# COMMUNICATION.net
KiCad netlist of a schematic drawn in Altium Designer
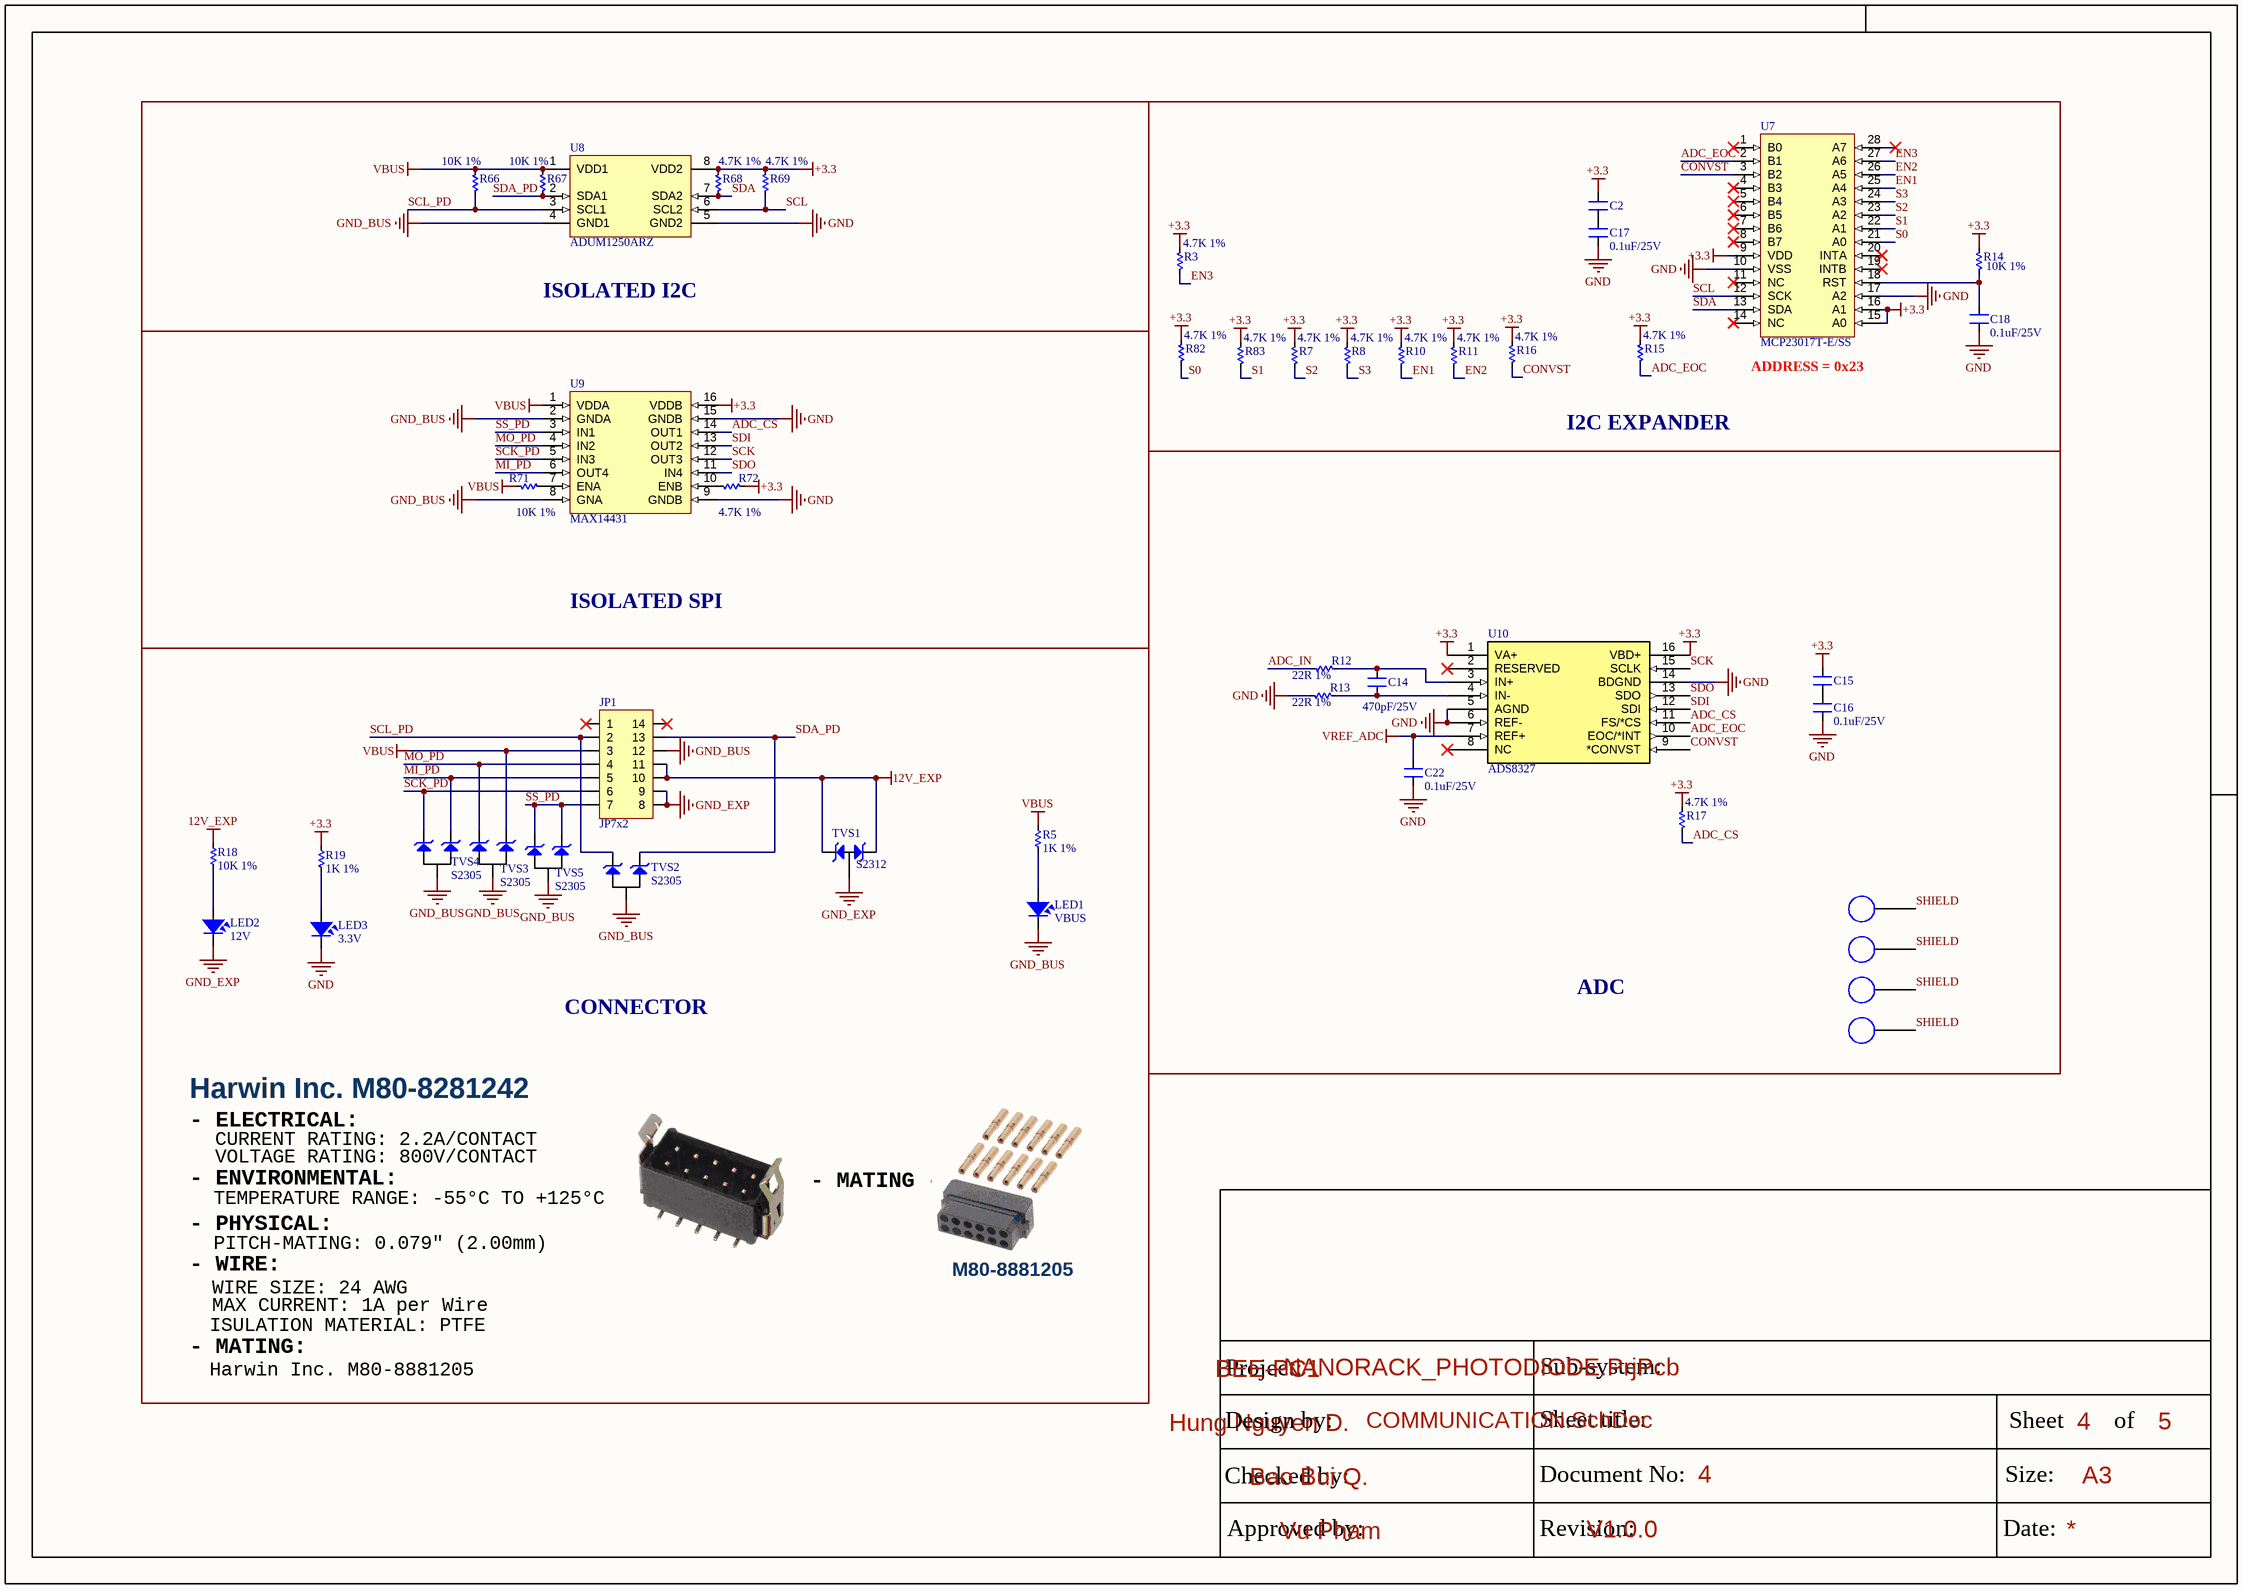
[diagram p0: COMMUNICATION.SchDoc]

(export (version "E")
  (design (tool "Eeschema 10.0.6"))
  (components
    (comp (ref "C2")
      (value "0.1uF/25V")
      (footprint "SM-0603")
      (description "0603")
      (libsource (lib "Capacitors") (part "CM"))
    )
    (comp (ref "C14")
      (value "470pF/25V")
      (footprint "SM-0603")
      (description "0603")
      (libsource (lib "Capacitors") (part "CM"))
    )
    (comp (ref "C15")
      (value "0.1uF/25V")
      (footprint "SM-0603")
      (description "0603")
      (libsource (lib "Capacitors") (part "CM"))
    )
    (comp (ref "C16")
      (value "0.1uF/25V")
      (footprint "SM-0603")
      (description "0603")
      (libsource (lib "Capacitors") (part "CM"))
    )
    (comp (ref "C17")
      (value "0.1uF/25V")
      (footprint "SM-0603")
      (description "0603")
      (libsource (lib "Capacitors") (part "CM"))
    )
    (comp (ref "C18")
      (value "0.1uF/25V")
      (footprint "SM-0603")
      (description "0603")
      (libsource (lib "Capacitors") (part "CM"))
    )
    (comp (ref "C22")
      (value "0.1uF/25V")
      (footprint "SM-0603")
      (description "0603")
      (libsource (lib "Capacitors") (part "CM"))
    )
    (comp (ref "H1") (value "M3") (footprint "M3") (libsource (lib "Library") (part "M3")))
    (comp (ref "H2") (value "M3") (footprint "M3") (libsource (lib "Library") (part "M3")))
    (comp (ref "H3") (value "M3") (footprint "M3") (libsource (lib "Library") (part "M3")))
    (comp (ref "H4") (value "M3") (footprint "M3") (libsource (lib "Library") (part "M3")))
    (comp (ref "JP1")
      (value "JP7x2")
      (footprint "M80-8281442")
      (description "WR-PHD 2.54 mm Dual Socket Header")
      (fields
        (field (name "MANUFACTURER") "Würth Elektronik eiSos GmbH")
        (field (name "PARTNO") "61301421821")
        (field (name "CREATED BY") "Karrer Zheng")
      )
      (libsource (lib "Library") (part "JP7x2"))
    )
    (comp (ref "LED1")
      (value "VBUS")
      (footprint "GREENLED_0603")
      (libsource (lib "Library") (part "LED SMD"))
    )
    (comp (ref "LED2") (value "12V") (footprint "GREENLED_0603") (libsource (lib "Library") (part "LED SMD")))
    (comp (ref "LED3")
      (value "3.3V")
      (footprint "GREENLED_0603")
      (libsource (lib "Library") (part "LED SMD"))
    )
    (comp (ref "R3")
      (value "4.7K 1%")
      (footprint "RES-SMD-0603")
      (description "0603")
      (fields
        (field (name "MANUFACTURER") "Generic Components")
        (field (name "PUBLISHER") "Altium Hobart Technology Centre")
      )
      (libsource (lib "Library") (part "Res-SMD"))
    )
    (comp (ref "R5")
      (value "1K 1%")
      (footprint "RES-SMD-0603")
      (description "0603")
      (fields
        (field (name "MANUFACTURER") "Generic Components")
        (field (name "PUBLISHER") "Altium Hobart Technology Centre")
      )
      (libsource (lib "Library") (part "Res-SMD"))
    )
    (comp (ref "R7")
      (value "4.7K 1%")
      (footprint "RES-SMD-0603")
      (description "0603")
      (fields
        (field (name "MANUFACTURER") "Generic Components")
        (field (name "PUBLISHER") "Altium Hobart Technology Centre")
      )
      (libsource (lib "Library") (part "Res-SMD"))
    )
    (comp (ref "R8")
      (value "4.7K 1%")
      (footprint "RES-SMD-0603")
      (description "0603")
      (fields
        (field (name "MANUFACTURER") "Generic Components")
        (field (name "PUBLISHER") "Altium Hobart Technology Centre")
      )
      (libsource (lib "Library") (part "Res-SMD"))
    )
    (comp (ref "R10")
      (value "4.7K 1%")
      (footprint "RES-SMD-0603")
      (description "0603")
      (fields
        (field (name "MANUFACTURER") "Generic Components")
        (field (name "PUBLISHER") "Altium Hobart Technology Centre")
      )
      (libsource (lib "Library") (part "Res-SMD"))
    )
    (comp (ref "R11")
      (value "4.7K 1%")
      (footprint "RES-SMD-0603")
      (description "0603")
      (fields
        (field (name "MANUFACTURER") "Generic Components")
        (field (name "PUBLISHER") "Altium Hobart Technology Centre")
      )
      (libsource (lib "Library") (part "Res-SMD"))
    )
    (comp (ref "R12")
      (value "22R 1%")
      (footprint "RES-SMD-0603")
      (description "0603")
      (fields
        (field (name "MANUFACTURER") "Generic Components")
        (field (name "PUBLISHER") "Altium Hobart Technology Centre")
      )
      (libsource (lib "Library") (part "Res-SMD"))
    )
    (comp (ref "R13")
      (value "22R 1%")
      (footprint "RES-SMD-0603")
      (description "0603")
      (fields
        (field (name "MANUFACTURER") "Generic Components")
        (field (name "PUBLISHER") "Altium Hobart Technology Centre")
      )
      (libsource (lib "Library") (part "Res-SMD"))
    )
    (comp (ref "R14")
      (value "10K 1%")
      (footprint "RES-SMD-0603")
      (description "0603")
      (fields
        (field (name "MANUFACTURER") "Generic Components")
        (field (name "PUBLISHER") "Altium Hobart Technology Centre")
      )
      (libsource (lib "Library") (part "Res-SMD"))
    )
    (comp (ref "R15")
      (value "4.7K 1%")
      (footprint "RES-SMD-0603")
      (description "0603")
      (fields
        (field (name "MANUFACTURER") "Generic Components")
        (field (name "PUBLISHER") "Altium Hobart Technology Centre")
      )
      (libsource (lib "Library") (part "Res-SMD"))
    )
    (comp (ref "R16")
      (value "4.7K 1%")
      (footprint "RES-SMD-0603")
      (description "0603")
      (fields
        (field (name "MANUFACTURER") "Generic Components")
        (field (name "PUBLISHER") "Altium Hobart Technology Centre")
      )
      (libsource (lib "Library") (part "Res-SMD"))
    )
    (comp (ref "R17")
      (value "4.7K 1%")
      (footprint "RES-SMD-0603")
      (description "0603")
      (fields
        (field (name "MANUFACTURER") "Generic Components")
        (field (name "PUBLISHER") "Altium Hobart Technology Centre")
      )
      (libsource (lib "Library") (part "Res-SMD"))
    )
    (comp (ref "R18")
      (value "10K 1%")
      (footprint "RES-SMD-0603")
      (description "0603")
      (fields
        (field (name "MANUFACTURER") "Generic Components")
        (field (name "PUBLISHER") "Altium Hobart Technology Centre")
      )
      (libsource (lib "Library") (part "Res-SMD"))
    )
    (comp (ref "R19")
      (value "1K 1%")
      (footprint "RES-SMD-0603")
      (description "0603")
      (fields
        (field (name "MANUFACTURER") "Generic Components")
        (field (name "PUBLISHER") "Altium Hobart Technology Centre")
      )
      (libsource (lib "Library") (part "Res-SMD"))
    )
    (comp (ref "R66")
      (value "10K 1%")
      (footprint "RES-SMD-0603")
      (description "0603")
      (fields
        (field (name "MANUFACTURER") "Generic Components")
        (field (name "PUBLISHER") "Altium Hobart Technology Centre")
      )
      (libsource (lib "Library") (part "Res-SMD"))
    )
    (comp (ref "R67")
      (value "10K 1%")
      (footprint "RES-SMD-0603")
      (description "0603")
      (fields
        (field (name "MANUFACTURER") "Generic Components")
        (field (name "PUBLISHER") "Altium Hobart Technology Centre")
      )
      (libsource (lib "Library") (part "Res-SMD"))
    )
    (comp (ref "R68")
      (value "4.7K 1%")
      (footprint "RES-SMD-0603")
      (description "0603")
      (fields
        (field (name "MANUFACTURER") "Generic Components")
        (field (name "PUBLISHER") "Altium Hobart Technology Centre")
      )
      (libsource (lib "Library") (part "Res-SMD"))
    )
    (comp (ref "R69")
      (value "4.7K 1%")
      (footprint "RES-SMD-0603")
      (description "0603")
      (fields
        (field (name "MANUFACTURER") "Generic Components")
        (field (name "PUBLISHER") "Altium Hobart Technology Centre")
      )
      (libsource (lib "Library") (part "Res-SMD"))
    )
    (comp (ref "R71")
      (value "10K 1%")
      (footprint "RES-SMD-0603")
      (description "0603")
      (fields
        (field (name "MANUFACTURER") "Generic Components")
        (field (name "PUBLISHER") "Altium Hobart Technology Centre")
      )
      (libsource (lib "Library") (part "Res-SMD"))
    )
    (comp (ref "R72")
      (value "4.7K 1%")
      (footprint "RES-SMD-0603")
      (description "0603")
      (fields
        (field (name "MANUFACTURER") "Generic Components")
        (field (name "PUBLISHER") "Altium Hobart Technology Centre")
      )
      (libsource (lib "Library") (part "Res-SMD"))
    )
    (comp (ref "R82")
      (value "4.7K 1%")
      (footprint "RES-SMD-0603")
      (description "0603")
      (fields
        (field (name "MANUFACTURER") "Generic Components")
        (field (name "PUBLISHER") "Altium Hobart Technology Centre")
      )
      (libsource (lib "Library") (part "Res-SMD"))
    )
    (comp (ref "R83")
      (value "4.7K 1%")
      (footprint "RES-SMD-0603")
      (description "0603")
      (fields
        (field (name "MANUFACTURER") "Generic Components")
        (field (name "PUBLISHER") "Altium Hobart Technology Centre")
      )
      (libsource (lib "Library") (part "Res-SMD"))
    )
    (comp (ref "TVS1")
      (value "S2312")
      (footprint "SOT23-123")
      (description "TVS DIODE 12VWM 19VC SOT23, P/N:  S2312")
      (libsource (lib "Library") (part "S2315"))
    )
    (comp (ref "TVS2")
      (value "S2305")
      (footprint "SOT23-123")
      (description "TVS DIODE 5VWM 10.8VC SOT23, P/N:  \r\nS2305")
      (libsource (lib "Library") (part "S2303"))
    )
    (comp (ref "TVS3")
      (value "S2305")
      (footprint "SOT23-123")
      (description "TVS DIODE 5VWM 10.8VC SOT23, P/N:  \r\nS2305")
      (libsource (lib "Library") (part "S2303"))
    )
    (comp (ref "TVS4")
      (value "S2305")
      (footprint "SOT23-123")
      (description "TVS DIODE 5VWM 10.8VC SOT23, P/N:  \r\nS2305")
      (libsource (lib "Library") (part "S2303"))
    )
    (comp (ref "TVS5")
      (value "S2305")
      (footprint "SOT23-123")
      (description "TVS DIODE 5VWM 10.8VC SOT23, P/N:  \r\nS2305")
      (libsource (lib "Library") (part "S2303"))
    )
    (comp (ref "U7")
      (value "MCP23017T-E/SS")
      (footprint "SSOP28")
      (libsource (lib "Library") (part "MCP23017"))
    )
    (comp (ref "U8") (value "ADUM1250ARZ") (footprint "SO8") (libsource (lib "Library") (part "ADUM1250")))
    (comp (ref "U9")
      (value "MAX14431")
      (footprint "MAX14431")
      (description "MAX14431CAEE+")
      (libsource (lib "Library") (part "MAX14431"))
    )
    (comp (ref "U10")
      (value "ADS8327")
      (footprint "TSSOP16")
      (description "IC ADC 16BIT SAR 16TSSOP")
      (libsource (lib "Library") (part "ADS8327"))
    )
  )
  (nets
    (net (code "1") (name "+3.3") (class "Default")
      (node (ref "C15") (pin "2") (pinfunction "2_2") (pintype "passive"))
      (node (ref "C2") (pin "2") (pinfunction "2_2") (pintype "passive"))
      (node (ref "R10") (pin "2") (pinfunction "2_2") (pintype "passive"))
      (node (ref "R11") (pin "2") (pinfunction "2_2") (pintype "passive"))
      (node (ref "R14") (pin "2") (pinfunction "2_2") (pintype "passive"))
      (node (ref "R15") (pin "2") (pinfunction "2_2") (pintype "passive"))
      (node (ref "R16") (pin "2") (pinfunction "2_2") (pintype "passive"))
      (node (ref "R17") (pin "2") (pinfunction "2_2") (pintype "passive"))
      (node (ref "R19") (pin "2") (pinfunction "2_2") (pintype "passive"))
      (node (ref "R3") (pin "2") (pinfunction "2_2") (pintype "passive"))
      (node (ref "R68") (pin "2") (pinfunction "2_2") (pintype "passive"))
      (node (ref "R69") (pin "2") (pinfunction "2_2") (pintype "passive"))
      (node (ref "R7") (pin "2") (pinfunction "2_2") (pintype "passive"))
      (node (ref "R72") (pin "1") (pinfunction "1_1") (pintype "passive"))
      (node (ref "R8") (pin "2") (pinfunction "2_2") (pintype "passive"))
      (node (ref "R82") (pin "2") (pinfunction "2_2") (pintype "passive"))
      (node (ref "R83") (pin "2") (pinfunction "2_2") (pintype "passive"))
      (node (ref "U10") (pin "1") (pinfunction "VA+_1") (pintype "power_in"))
      (node (ref "U10") (pin "16") (pinfunction "VBD+_16") (pintype "power_in"))
      (node (ref "U7") (pin "15") (pinfunction "A0_15") (pintype "input"))
      (node (ref "U7") (pin "16") (pinfunction "A1_16") (pintype "input"))
      (node (ref "U7") (pin "9") (pinfunction "VDD_9") (pintype "input"))
      (node (ref "U8") (pin "8") (pinfunction "VDD2_8") (pintype "power_in"))
      (node (ref "U9") (pin "16") (pinfunction "VDDB_16") (pintype "input"))
    )
    (net (code "2") (name "/ADC_CS") (class "Default")
      (node (ref "R17") (pin "1") (pinfunction "1_1") (pintype "passive"))
      (node (ref "U10") (pin "11") (pinfunction "FS/*CS_11") (pintype "input"))
      (node (ref "U9") (pin "14") (pinfunction "OUT1_14") (pintype "input"))
    )
    (net (code "3") (name "/ADC_EOC") (class "Default")
      (node (ref "R15") (pin "1") (pinfunction "1_1") (pintype "passive"))
      (node (ref "U10") (pin "10") (pinfunction "EOC/*INT_10") (pintype "output"))
      (node (ref "U7") (pin "2") (pinfunction "B1_2") (pintype "input"))
    )
    (net (code "4") (name "/ADC_IN") (class "Default")
      (node (ref "R12") (pin "2") (pinfunction "2_2") (pintype "passive"))
    )
    (net (code "5") (name "/CONVST") (class "Default")
      (node (ref "R16") (pin "1") (pinfunction "1_1") (pintype "passive"))
      (node (ref "U10") (pin "9") (pinfunction "*CONVST_9") (pintype "input"))
      (node (ref "U7") (pin "3") (pinfunction "B2_3") (pintype "input"))
    )
    (net (code "6") (name "/EN1") (class "Default")
      (node (ref "R10") (pin "1") (pinfunction "1_1") (pintype "passive"))
      (node (ref "U7") (pin "25") (pinfunction "A4_25") (pintype "input"))
    )
    (net (code "7") (name "/EN2") (class "Default")
      (node (ref "R11") (pin "1") (pinfunction "1_1") (pintype "passive"))
      (node (ref "U7") (pin "26") (pinfunction "A5_26") (pintype "input"))
    )
    (net (code "8") (name "/EN3") (class "Default")
      (node (ref "R3") (pin "1") (pinfunction "1_1") (pintype "passive"))
      (node (ref "U7") (pin "27") (pinfunction "A6_27") (pintype "input"))
    )
    (net (code "9") (name "/MI_PD") (class "Default")
      (node (ref "JP1") (pin "5") (pinfunction "5_5") (pintype "passive"))
      (node (ref "TVS4") (pin "3") (pintype "passive"))
      (node (ref "U9") (pin "6") (pinfunction "OUT4_6") (pintype "input"))
    )
    (net (code "10") (name "/MO_PD") (class "Default")
      (node (ref "JP1") (pin "4") (pinfunction "4_4") (pintype "passive"))
      (node (ref "TVS3") (pin "1") (pintype "passive"))
      (node (ref "U9") (pin "4") (pinfunction "IN2_4") (pintype "input"))
    )
    (net (code "11") (name "/S0") (class "Default")
      (node (ref "R82") (pin "1") (pinfunction "1_1") (pintype "passive"))
      (node (ref "U7") (pin "21") (pinfunction "A0_21") (pintype "input"))
    )
    (net (code "12") (name "/S1") (class "Default")
      (node (ref "R83") (pin "1") (pinfunction "1_1") (pintype "passive"))
      (node (ref "U7") (pin "22") (pinfunction "A1_22") (pintype "input"))
    )
    (net (code "13") (name "/S2") (class "Default")
      (node (ref "R7") (pin "1") (pinfunction "1_1") (pintype "passive"))
      (node (ref "U7") (pin "23") (pinfunction "A2_23") (pintype "input"))
    )
    (net (code "14") (name "/S3") (class "Default")
      (node (ref "R8") (pin "1") (pinfunction "1_1") (pintype "passive"))
      (node (ref "U7") (pin "24") (pinfunction "A3_24") (pintype "input"))
    )
    (net (code "15") (name "/SCK") (class "Default")
      (node (ref "U10") (pin "15") (pinfunction "SCLK_15") (pintype "input"))
      (node (ref "U9") (pin "12") (pinfunction "OUT3_12") (pintype "input"))
    )
    (net (code "16") (name "/SCK_PD") (class "Default")
      (node (ref "JP1") (pin "6") (pinfunction "6_6") (pintype "passive"))
      (node (ref "TVS4") (pin "1") (pintype "passive"))
      (node (ref "U9") (pin "5") (pinfunction "IN3_5") (pintype "input"))
    )
    (net (code "17") (name "/SCL") (class "Default")
      (node (ref "R69") (pin "1") (pinfunction "1_1") (pintype "passive"))
      (node (ref "U7") (pin "12") (pinfunction "SCK_12") (pintype "input"))
      (node (ref "U8") (pin "6") (pinfunction "SCL2_6") (pintype "input"))
    )
    (net (code "18") (name "/SCL_PD") (class "Default")
      (node (ref "JP1") (pin "2") (pinfunction "2_2") (pintype "passive"))
      (node (ref "R66") (pin "1") (pinfunction "1_1") (pintype "passive"))
      (node (ref "TVS2") (pin "1") (pintype "passive"))
      (node (ref "U8") (pin "3") (pinfunction "SCL1_3") (pintype "input"))
    )
    (net (code "19") (name "/SDA") (class "Default")
      (node (ref "R68") (pin "1") (pinfunction "1_1") (pintype "passive"))
      (node (ref "U7") (pin "13") (pinfunction "SDA_13") (pintype "input"))
      (node (ref "U8") (pin "7") (pinfunction "SDA2_7") (pintype "input"))
    )
    (net (code "20") (name "/SDA_PD") (class "Default")
      (node (ref "JP1") (pin "13") (pinfunction "13_13") (pintype "passive"))
      (node (ref "R67") (pin "1") (pinfunction "1_1") (pintype "passive"))
      (node (ref "TVS2") (pin "3") (pintype "passive"))
      (node (ref "U8") (pin "2") (pinfunction "SDA1_2") (pintype "input"))
    )
    (net (code "21") (name "/SDI") (class "Default")
      (node (ref "U10") (pin "12") (pinfunction "SDI_12") (pintype "input"))
      (node (ref "U9") (pin "13") (pinfunction "OUT2_13") (pintype "input"))
    )
    (net (code "22") (name "/SDO") (class "Default")
      (node (ref "U10") (pin "13") (pinfunction "SDO_13") (pintype "output"))
      (node (ref "U9") (pin "11") (pinfunction "IN4_11") (pintype "input"))
    )
    (net (code "23") (name "/SHIELD") (class "Default")
      (node (ref "H1") (pin "1") (pinfunction "76_1") (pintype "passive"))
      (node (ref "H2") (pin "1") (pinfunction "76_1") (pintype "passive"))
      (node (ref "H3") (pin "1") (pinfunction "76_1") (pintype "passive"))
      (node (ref "H4") (pin "1") (pinfunction "76_1") (pintype "passive"))
    )
    (net (code "24") (name "/SS_PD") (class "Default")
      (node (ref "JP1") (pin "7") (pinfunction "7_7") (pintype "passive"))
      (node (ref "TVS5") (pin "1") (pintype "passive"))
      (node (ref "TVS5") (pin "3") (pintype "passive"))
      (node (ref "U9") (pin "3") (pinfunction "IN1_3") (pintype "input"))
    )
    (net (code "25") (name "12V_EXP") (class "Default")
      (node (ref "JP1") (pin "10") (pinfunction "10_10") (pintype "passive"))
      (node (ref "JP1") (pin "11") (pinfunction "11_11") (pintype "passive"))
      (node (ref "R18") (pin "2") (pinfunction "2_2") (pintype "passive"))
      (node (ref "TVS1") (pin "1") (pintype "passive"))
      (node (ref "TVS1") (pin "3") (pintype "passive"))
    )
    (net (code "26") (name "GND") (class "Default")
      (node (ref "C16") (pin "1") (pinfunction "1_1") (pintype "passive"))
      (node (ref "C17") (pin "1") (pinfunction "1_1") (pintype "passive"))
      (node (ref "C18") (pin "1") (pinfunction "1_1") (pintype "passive"))
      (node (ref "C22") (pin "1") (pinfunction "1_1") (pintype "passive"))
      (node (ref "LED3") (pin "2") (pinfunction "2_2") (pintype "passive"))
      (node (ref "R13") (pin "2") (pinfunction "2_2") (pintype "passive"))
      (node (ref "U10") (pin "14") (pinfunction "BDGND_14") (pintype "power_in"))
      (node (ref "U10") (pin "5") (pinfunction "AGND_5") (pintype "power_in"))
      (node (ref "U10") (pin "6") (pinfunction "REF-_6") (pintype "input"))
      (node (ref "U7") (pin "10") (pinfunction "VSS_10") (pintype "input"))
      (node (ref "U7") (pin "17") (pinfunction "A2_17") (pintype "input"))
      (node (ref "U8") (pin "5") (pinfunction "GND2_5") (pintype "power_in"))
      (node (ref "U9") (pin "15") (pinfunction "GNDB_15") (pintype "input"))
      (node (ref "U9") (pin "9") (pinfunction "GNDB_9") (pintype "input"))
    )
    (net (code "27") (name "GND_BUS") (class "Default")
      (node (ref "JP1") (pin "12") (pinfunction "12_12") (pintype "passive"))
      (node (ref "LED1") (pin "2") (pinfunction "2_2") (pintype "passive"))
      (node (ref "TVS2") (pin "2") (pintype "passive"))
      (node (ref "TVS3") (pin "2") (pintype "passive"))
      (node (ref "TVS4") (pin "2") (pintype "passive"))
      (node (ref "TVS5") (pin "2") (pintype "passive"))
      (node (ref "U8") (pin "4") (pinfunction "GND1_4") (pintype "power_in"))
      (node (ref "U9") (pin "2") (pinfunction "GNDA_2") (pintype "input"))
      (node (ref "U9") (pin "8") (pinfunction "GNA_8") (pintype "input"))
    )
    (net (code "28") (name "GND_EXP") (class "Default")
      (node (ref "JP1") (pin "8") (pinfunction "8_8") (pintype "passive"))
      (node (ref "JP1") (pin "9") (pinfunction "9_9") (pintype "passive"))
      (node (ref "LED2") (pin "2") (pinfunction "2_2") (pintype "passive"))
      (node (ref "TVS1") (pin "2") (pintype "passive"))
    )
    (net (code "29") (name "Net-(C15-Pad1)") (class "Default")
      (node (ref "C15") (pin "1") (pinfunction "1_1") (pintype "passive"))
      (node (ref "C16") (pin "2") (pinfunction "2_2") (pintype "passive"))
    )
    (net (code "30") (name "Net-(C17-Pad2)") (class "Default")
      (node (ref "C17") (pin "2") (pinfunction "2_2") (pintype "passive"))
      (node (ref "C2") (pin "1") (pinfunction "1_1") (pintype "passive"))
    )
    (net (code "31") (name "Net-(LED1-Pad1)") (class "Default")
      (node (ref "LED1") (pin "1") (pinfunction "1_1") (pintype "passive"))
      (node (ref "R5") (pin "1") (pinfunction "1_1") (pintype "passive"))
    )
    (net (code "32") (name "Net-(LED2-Pad1)") (class "Default")
      (node (ref "LED2") (pin "1") (pinfunction "1_1") (pintype "passive"))
      (node (ref "R18") (pin "1") (pinfunction "1_1") (pintype "passive"))
    )
    (net (code "33") (name "Net-(LED3-Pad1)") (class "Default")
      (node (ref "LED3") (pin "1") (pinfunction "1_1") (pintype "passive"))
      (node (ref "R19") (pin "1") (pinfunction "1_1") (pintype "passive"))
    )
    (net (code "34") (name "Net-(U7-RST)") (class "Default")
      (node (ref "C18") (pin "2") (pinfunction "2_2") (pintype "passive"))
      (node (ref "R14") (pin "1") (pinfunction "1_1") (pintype "passive"))
      (node (ref "U7") (pin "18") (pinfunction "RST_18") (pintype "input"))
    )
    (net (code "35") (name "Net-(U9-ENA)") (class "Default")
      (node (ref "R71") (pin "1") (pinfunction "1_1") (pintype "passive"))
      (node (ref "U9") (pin "7") (pinfunction "ENA_7") (pintype "input"))
    )
    (net (code "36") (name "Net-(U9-ENB)") (class "Default")
      (node (ref "R72") (pin "2") (pinfunction "2_2") (pintype "passive"))
      (node (ref "U9") (pin "10") (pinfunction "ENB_10") (pintype "input"))
    )
    (net (code "37") (name "Net-(U10-IN+)") (class "Default")
      (node (ref "C14") (pin "2") (pinfunction "2_2") (pintype "passive"))
      (node (ref "R12") (pin "1") (pinfunction "1_1") (pintype "passive"))
      (node (ref "U10") (pin "3") (pinfunction "IN+_3") (pintype "input"))
    )
    (net (code "38") (name "Net-(U10-IN-)") (class "Default")
      (node (ref "C14") (pin "1") (pinfunction "1_1") (pintype "passive"))
      (node (ref "R13") (pin "1") (pinfunction "1_1") (pintype "passive"))
      (node (ref "U10") (pin "4") (pinfunction "IN-_4") (pintype "input"))
    )
    (net (code "39") (name "VBUS") (class "Default")
      (node (ref "JP1") (pin "3") (pinfunction "3_3") (pintype "passive"))
      (node (ref "R5") (pin "2") (pinfunction "2_2") (pintype "passive"))
      (node (ref "R66") (pin "2") (pinfunction "2_2") (pintype "passive"))
      (node (ref "R67") (pin "2") (pinfunction "2_2") (pintype "passive"))
      (node (ref "R71") (pin "2") (pinfunction "2_2") (pintype "passive"))
      (node (ref "TVS3") (pin "3") (pintype "passive"))
      (node (ref "U8") (pin "1") (pinfunction "VDD1_1") (pintype "power_in"))
      (node (ref "U9") (pin "1") (pinfunction "VDDA_1") (pintype "input"))
    )
    (net (code "40") (name "VREF_ADC") (class "Default")
      (node (ref "C22") (pin "2") (pinfunction "2_2") (pintype "passive"))
      (node (ref "U10") (pin "7") (pinfunction "REF+_7") (pintype "input"))
    )
    (net (code "41") (name "unconnected-(JP1-Pad1)") (class "Default")
      (node (ref "JP1") (pin "1") (pinfunction "1_1") (pintype "passive+no_connect"))
    )
    (net (code "42") (name "unconnected-(JP1-Pad14)") (class "Default")
      (node (ref "JP1") (pin "14") (pinfunction "14_14") (pintype "passive+no_connect"))
    )
    (net (code "43") (name "unconnected-(U7-A7-Pad28)") (class "Default")
      (node (ref "U7") (pin "28") (pinfunction "A7_28") (pintype "input+no_connect"))
    )
    (net (code "44") (name "unconnected-(U7-B0-Pad1)") (class "Default")
      (node (ref "U7") (pin "1") (pinfunction "B0_1") (pintype "input+no_connect"))
    )
    (net (code "45") (name "unconnected-(U7-B3-Pad4)") (class "Default")
      (node (ref "U7") (pin "4") (pinfunction "B3_4") (pintype "input+no_connect"))
    )
    (net (code "46") (name "unconnected-(U7-B4-Pad5)") (class "Default")
      (node (ref "U7") (pin "5") (pinfunction "B4_5") (pintype "input+no_connect"))
    )
    (net (code "47") (name "unconnected-(U7-B5-Pad6)") (class "Default")
      (node (ref "U7") (pin "6") (pinfunction "B5_6") (pintype "input+no_connect"))
    )
    (net (code "48") (name "unconnected-(U7-B6-Pad7)") (class "Default")
      (node (ref "U7") (pin "7") (pinfunction "B6_7") (pintype "input+no_connect"))
    )
    (net (code "49") (name "unconnected-(U7-B7-Pad8)") (class "Default")
      (node (ref "U7") (pin "8") (pinfunction "B7_8") (pintype "input+no_connect"))
    )
    (net (code "50") (name "unconnected-(U7-INTA-Pad20)") (class "Default")
      (node (ref "U7") (pin "20") (pinfunction "INTA_20") (pintype "input+no_connect"))
    )
    (net (code "51") (name "unconnected-(U7-INTB-Pad19)") (class "Default")
      (node (ref "U7") (pin "19") (pinfunction "INTB_19") (pintype "input+no_connect"))
    )
    (net (code "52") (name "unconnected-(U7-NC-Pad11)") (class "Default")
      (node (ref "U7") (pin "11") (pinfunction "NC_11") (pintype "input+no_connect"))
    )
    (net (code "53") (name "unconnected-(U7-NC-Pad14)") (class "Default")
      (node (ref "U7") (pin "14") (pinfunction "NC_14") (pintype "input+no_connect"))
    )
    (net (code "54") (name "unconnected-(U10-NC-Pad8)") (class "Default")
      (node (ref "U10") (pin "8") (pinfunction "NC_8") (pintype "passive+no_connect"))
    )
    (net (code "55") (name "unconnected-(U10-RESERVED-Pad2)") (class "Default")
      (node (ref "U10") (pin "2") (pinfunction "RESERVED_2") (pintype "passive+no_connect"))
    )
  )
)
